# Reset_Bootloader_and_Mounting.net
KiCad netlist of a schematic drawn in Altium Designer
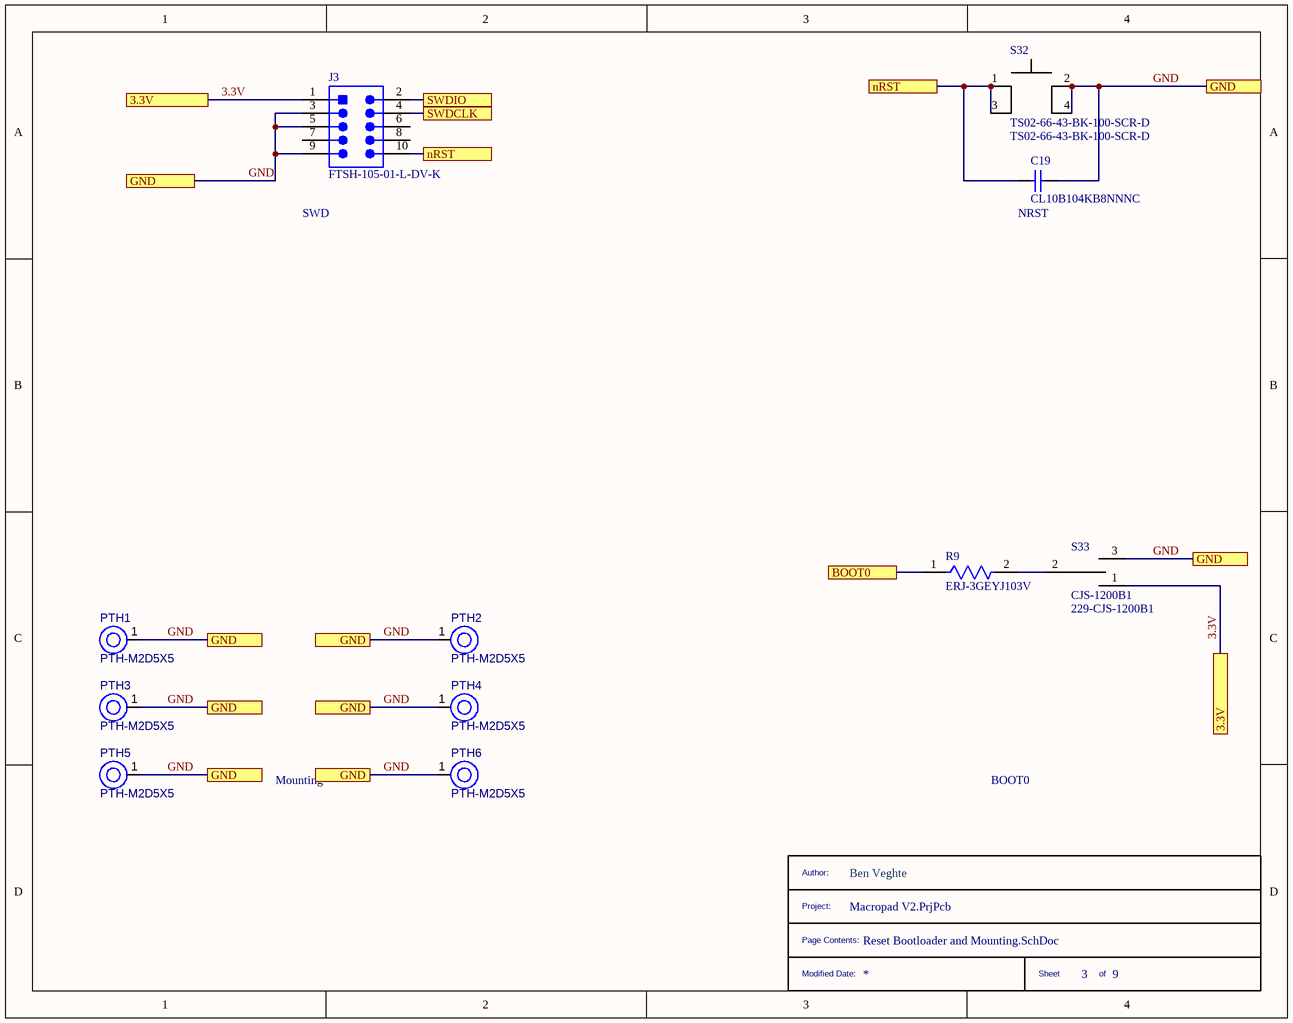
[diagram p0: Reset Bootloader and Mounting.SchDoc]

(export (version "E")
  (design (tool "Eeschema 10.0.6"))
  (components
    (comp (ref "C19")
      (value "CL10B104KB8NNNC")
      (footprint "SAMS-C0603-2_M")
      (description "Multi-layer Ceramic Capacitor, -55 to 125 degC, 2-Pin SMD (0603), RoHS, Tape and Reel")
      (fields (field (name "MANUFACTURER") "Samsung Electro-Mechanics"))
      (libsource (lib "Altium Content Vault") (part "CAP-NP-2"))
    )
    (comp (ref "J3")
      (value "FTSH-105-01-L-DV-K")
      (footprint "SMTC-FTSH-105-01-L-DV-K_V")
      (description "Male Header, Pitch 1.27 mm, 2 x 5 Position, Height 6.25 mm")
      (fields (field (name "MANUFACTURER") "Samtec"))
      (libsource (lib "Altium Content Vault") (part "CN-2P-M-R10"))
    )
    (comp (ref "PTH1")
      (value "PTH-M2D5X5")
      (footprint "PTH-M2D5X5")
      (description "M2 PTH (2.5mm), 5mm pad")
      (libsource (lib "AerospaceNU") (part "CMP-00028-00000-1"))
    )
    (comp (ref "PTH2")
      (value "PTH-M2D5X5")
      (footprint "PTH-M2D5X5")
      (description "M2 PTH (2.5mm), 5mm pad")
      (libsource (lib "AerospaceNU") (part "CMP-00028-00000-1"))
    )
    (comp (ref "PTH3")
      (value "PTH-M2D5X5")
      (footprint "PTH-M2D5X5")
      (description "M2 PTH (2.5mm), 5mm pad")
      (libsource (lib "AerospaceNU") (part "CMP-00028-00000-1"))
    )
    (comp (ref "PTH4")
      (value "PTH-M2D5X5")
      (footprint "PTH-M2D5X5")
      (description "M2 PTH (2.5mm), 5mm pad")
      (libsource (lib "AerospaceNU") (part "CMP-00028-00000-1"))
    )
    (comp (ref "PTH5")
      (value "PTH-M2D5X5")
      (footprint "PTH-M2D5X5")
      (description "M2 PTH (2.5mm), 5mm pad")
      (libsource (lib "AerospaceNU") (part "CMP-00028-00000-1"))
    )
    (comp (ref "PTH6")
      (value "PTH-M2D5X5")
      (footprint "PTH-M2D5X5")
      (description "M2 PTH (2.5mm), 5mm pad")
      (libsource (lib "AerospaceNU") (part "CMP-00028-00000-1"))
    )
    (comp (ref "R9")
      (value "ERJ-3GEYJ103V")
      (footprint "FP-ERJ3G-IPC_C")
      (description "RES SMD 10K OHM 5% 1/10W 0603")
      (fields (field (name "TOLERANCE") "5%"))
      (libsource (lib "Altium Content Vault") (part "1029c3af85768c4190bb7ad29bc67b5"))
    )
    (comp (ref "S32")
      (value "TS02-66-43-BK-100-SCR-D")
      (footprint "TS02-66-43-BK-100-SCR-D")
      (description "Switch Tactile OFF (ON) SPST Round Button PC Pins 0.05A 12VDC 100000Cycles 1N Thru-Hole Bag")
      (fields
        (field (name "MANUFACTURER") "CUI Devices")
        (field (name "SUPPLIER PART NUMBER 1") "TS02-66-43-BK-100-SCR-D")
      )
      (libsource (lib "Universal Parts") (part "TS02-66-43-BK-100-SCR-D"))
    )
    (comp (ref "S33")
      (value "CJS-1200B1")
      (footprint "CJS-1200B1")
      (description "Switch Slide N.O./N.C. SPDT Raised Slide 0.1A 24VDC Gull Wing SMD Bulk")
      (fields
        (field (name "MANUFACTURER") "CUI")
        (field (name "MANUFACTURER PART NUMBER") "DS01-254-L-01BE")
        (field (name "SUPPLIER PART NUMBER 2") "229-CJS-1200B1")
      )
      (libsource (lib "Universal Parts") (part "CJS-1200B1"))
    )
  )
  (nets
    (net (code "1") (name "/3.3V") (class "Default")
      (node (ref "J3") (pin "1") (pinfunction "1_1") (pintype "passive"))
      (node (ref "S33") (pin "1") (pinfunction "1_1") (pintype "passive"))
    )
    (net (code "2") (name "/BOOT0") (class "Default")
      (node (ref "R9") (pin "1") (pinfunction "1_1") (pintype "passive"))
    )
    (net (code "3") (name "/GND") (class "Default")
      (node (ref "C19") (pin "2") (pinfunction "2_2") (pintype "passive"))
      (node (ref "J3") (pin "3") (pinfunction "3_3") (pintype "passive"))
      (node (ref "J3") (pin "5") (pinfunction "5_5") (pintype "passive"))
      (node (ref "J3") (pin "9") (pinfunction "9_9") (pintype "passive"))
      (node (ref "PTH1") (pin "1") (pinfunction "H1_1") (pintype "passive"))
      (node (ref "PTH2") (pin "1") (pinfunction "H1_1") (pintype "passive"))
      (node (ref "PTH3") (pin "1") (pinfunction "H1_1") (pintype "passive"))
      (node (ref "PTH4") (pin "1") (pinfunction "H1_1") (pintype "passive"))
      (node (ref "PTH5") (pin "1") (pinfunction "H1_1") (pintype "passive"))
      (node (ref "PTH6") (pin "1") (pinfunction "H1_1") (pintype "passive"))
      (node (ref "S32") (pin "2") (pinfunction "2_2") (pintype "passive"))
      (node (ref "S32") (pin "4") (pinfunction "4_4") (pintype "passive"))
      (node (ref "S33") (pin "3") (pinfunction "3_3") (pintype "passive"))
    )
    (net (code "4") (name "/SWDCLK") (class "Default")
      (node (ref "J3") (pin "4") (pinfunction "4_4") (pintype "passive"))
    )
    (net (code "5") (name "/SWDIO") (class "Default")
      (node (ref "J3") (pin "2") (pinfunction "2_2") (pintype "passive"))
    )
    (net (code "6") (name "/nRST") (class "Default")
      (node (ref "C19") (pin "1") (pinfunction "1_1") (pintype "passive"))
      (node (ref "J3") (pin "10") (pinfunction "10_10") (pintype "passive"))
      (node (ref "S32") (pin "1") (pinfunction "1_1") (pintype "passive"))
      (node (ref "S32") (pin "3") (pinfunction "3_3") (pintype "passive"))
    )
    (net (code "7") (name "Net-(R9-Pad2)") (class "Default")
      (node (ref "R9") (pin "2") (pinfunction "2_2") (pintype "passive"))
      (node (ref "S33") (pin "2") (pinfunction "2_2") (pintype "passive"))
    )
    (net (code "8") (name "unconnected-(J3-Pad6)") (class "Default")
      (node (ref "J3") (pin "6") (pinfunction "6_6") (pintype "passive"))
    )
    (net (code "9") (name "unconnected-(J3-Pad7)") (class "Default")
      (node (ref "J3") (pin "7") (pinfunction "7_7") (pintype "passive"))
    )
    (net (code "10") (name "unconnected-(J3-Pad8)") (class "Default")
      (node (ref "J3") (pin "8") (pinfunction "8_8") (pintype "passive"))
    )
  )
)
